# controller.net
KiCad netlist of a schematic drawn in EAGLE
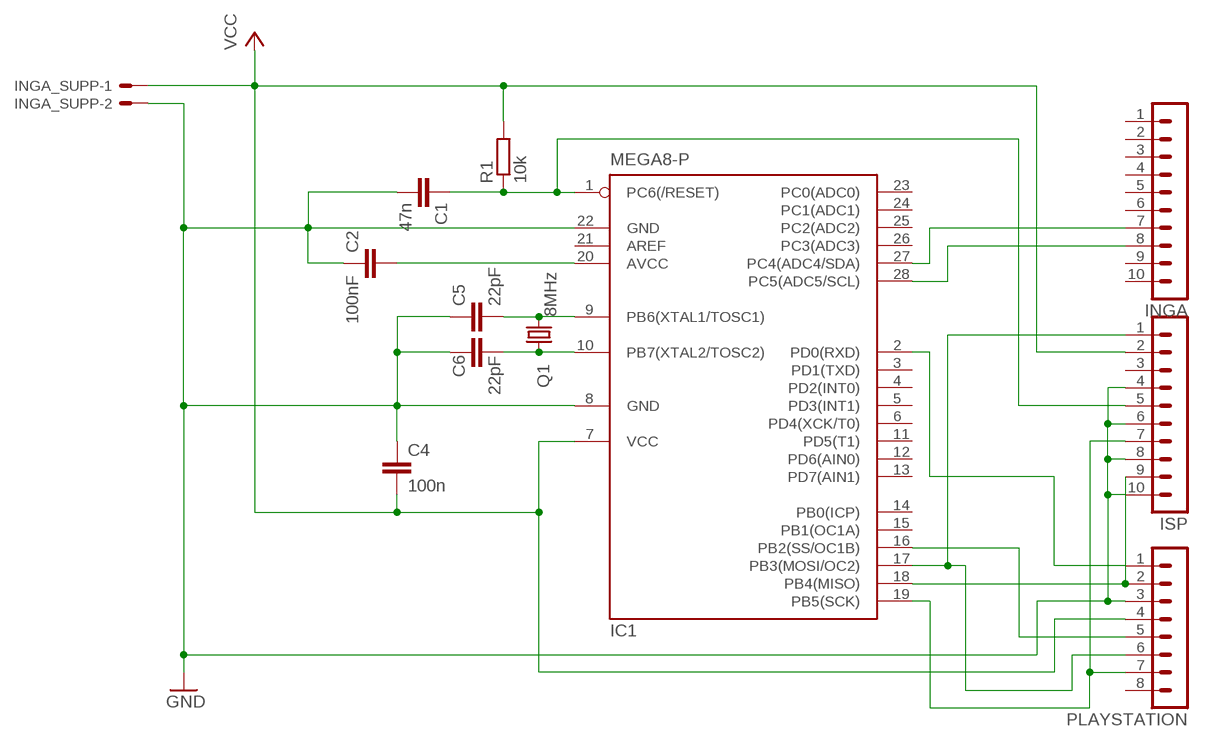
[diagram p0: schematic, sheet 1]

(export (version "E")
  (design (tool "Eeschema 10.0.6"))
  (components
    (comp (ref "C1")
      (value "47n")
      (footprint "eagle-import:C2.5-3")
      (libsource (lib "eagle-import") (part "C2,5-3"))
    )
    (comp (ref "C2")
      (value "100nF")
      (footprint "eagle-import:C2.5-3")
      (libsource (lib "eagle-import") (part "C2,5-3"))
    )
    (comp (ref "C4")
      (value "100n")
      (footprint "eagle-import:C2.5-3")
      (libsource (lib "eagle-import") (part "C2,5-3"))
    )
    (comp (ref "C5")
      (value "22pF")
      (footprint "eagle-import:C2.5-3")
      (libsource (lib "eagle-import") (part "C2,5-3"))
    )
    (comp (ref "C6")
      (value "22pF")
      (footprint "eagle-import:C2.5-3")
      (libsource (lib "eagle-import") (part "C2,5-3"))
    )
    (comp (ref "IC1")
      (value "MEGA8-P")
      (footprint "eagle-import:DIL28-3")
      (libsource (lib "eagle-import") (part "MEGA8-P"))
    )
    (comp (ref "INGA")
      (value "MA10-1")
      (footprint "eagle-import:MA10-1")
      (libsource (lib "eagle-import") (part "MA10-1"))
    )
    (comp (ref "INGA_SUPP")
      (value "22-23-2021")
      (footprint "eagle-import:22-23-2021")
      (fields (field (name "MF") "MOLEX"))
      (libsource (lib "eagle-import") (part "22-23-2021"))
    )
    (comp (ref "ISP")
      (value "MA10-1")
      (footprint "eagle-import:MA10-1")
      (libsource (lib "eagle-import") (part "MA10-1"))
    )
    (comp (ref "PLAYSTATION")
      (value "MA08-1")
      (footprint "eagle-import:MA08-1")
      (libsource (lib "eagle-import") (part "MA08-1"))
    )
    (comp (ref "Q1")
      (value "8MHz")
      (footprint "eagle-import:HC49U70")
      (libsource (lib "eagle-import") (part "CRYSTALHC49U70"))
    )
    (comp (ref "R1")
      (value "10k")
      (footprint "eagle-import:0207_10")
      (libsource (lib "eagle-import") (part "R-EU_0207/10"))
    )
  )
  (nets
    (net (code "1") (name "GND") (class "Default")
      (node (ref "C1") (pin "2") (pinfunction "2_2") (pintype "passive"))
      (node (ref "C2") (pin "1") (pinfunction "1_1") (pintype "passive"))
      (node (ref "C4") (pin "1") (pinfunction "1_1") (pintype "passive"))
      (node (ref "C5") (pin "1") (pinfunction "1_1") (pintype "passive"))
      (node (ref "C6") (pin "1") (pinfunction "1_1") (pintype "passive"))
      (node (ref "IC1") (pin "22") (pinfunction "GND_22") (pintype "power_in"))
      (node (ref "IC1") (pin "8") (pinfunction "GND_8") (pintype "power_in"))
      (node (ref "INGA_SUPP") (pin "2") (pinfunction "S_2") (pintype "passive"))
      (node (ref "ISP") (pin "10") (pinfunction "10_10") (pintype "passive"))
      (node (ref "ISP") (pin "4") (pinfunction "4_4") (pintype "passive"))
      (node (ref "ISP") (pin "6") (pinfunction "6_6") (pintype "passive"))
      (node (ref "ISP") (pin "8") (pinfunction "8_8") (pintype "passive"))
      (node (ref "PLAYSTATION") (pin "3") (pinfunction "3_3") (pintype "passive"))
    )
    (net (code "2") (name "Net-(IC1-AVCC)") (class "Default")
      (node (ref "C2") (pin "2") (pinfunction "2_2") (pintype "passive"))
      (node (ref "IC1") (pin "20") (pinfunction "AVCC_20") (pintype "power_in"))
    )
    (net (code "3") (name "Net-(IC1-PB2(SS{slash}OC1B))") (class "Default")
      (node (ref "IC1") (pin "16") (pinfunction "PB2(SS/OC1B)_16") (pintype "bidirectional"))
      (node (ref "PLAYSTATION") (pin "5") (pinfunction "5_5") (pintype "passive"))
    )
    (net (code "4") (name "Net-(IC1-PB3(MOSI{slash}OC2))") (class "Default")
      (node (ref "IC1") (pin "17") (pinfunction "PB3(MOSI/OC2)_17") (pintype "bidirectional"))
      (node (ref "ISP") (pin "1") (pinfunction "1_1") (pintype "passive"))
      (node (ref "PLAYSTATION") (pin "6") (pinfunction "6_6") (pintype "passive"))
    )
    (net (code "5") (name "Net-(IC1-PB4(MISO))") (class "Default")
      (node (ref "IC1") (pin "18") (pinfunction "PB4(MISO)_18") (pintype "bidirectional"))
      (node (ref "ISP") (pin "9") (pinfunction "9_9") (pintype "passive"))
      (node (ref "PLAYSTATION") (pin "2") (pinfunction "2_2") (pintype "passive"))
    )
    (net (code "6") (name "Net-(IC1-PB5(SCK))") (class "Default")
      (node (ref "IC1") (pin "19") (pinfunction "PB5(SCK)_19") (pintype "bidirectional"))
      (node (ref "ISP") (pin "7") (pinfunction "7_7") (pintype "passive"))
      (node (ref "PLAYSTATION") (pin "7") (pinfunction "7_7") (pintype "passive"))
    )
    (net (code "7") (name "Net-(IC1-PB6(XTAL1{slash}TOSC1))") (class "Default")
      (node (ref "C5") (pin "2") (pinfunction "2_2") (pintype "passive"))
      (node (ref "IC1") (pin "9") (pinfunction "PB6(XTAL1/TOSC1)_9") (pintype "bidirectional"))
      (node (ref "Q1") (pin "2") (pinfunction "2_2") (pintype "passive"))
    )
    (net (code "8") (name "Net-(IC1-PB7(XTAL2{slash}TOSC2))") (class "Default")
      (node (ref "C6") (pin "2") (pinfunction "2_2") (pintype "passive"))
      (node (ref "IC1") (pin "10") (pinfunction "PB7(XTAL2/TOSC2)_10") (pintype "bidirectional"))
      (node (ref "Q1") (pin "1") (pinfunction "1_1") (pintype "passive"))
    )
    (net (code "9") (name "Net-(IC1-PC4(ADC4{slash}SDA))") (class "Default")
      (node (ref "IC1") (pin "27") (pinfunction "PC4(ADC4/SDA)_27") (pintype "bidirectional"))
      (node (ref "INGA") (pin "7") (pinfunction "7_7") (pintype "passive"))
    )
    (net (code "10") (name "Net-(IC1-PC5(ADC5{slash}SCL))") (class "Default")
      (node (ref "IC1") (pin "28") (pinfunction "PC5(ADC5/SCL)_28") (pintype "bidirectional"))
      (node (ref "INGA") (pin "8") (pinfunction "8_8") (pintype "passive"))
    )
    (net (code "11") (name "Net-(IC1-PC6({slash}RESET))") (class "Default")
      (node (ref "C1") (pin "1") (pinfunction "1_1") (pintype "passive"))
      (node (ref "IC1") (pin "1") (pinfunction "PC6(/RESET)_1") (pintype "bidirectional"))
      (node (ref "ISP") (pin "5") (pinfunction "5_5") (pintype "passive"))
      (node (ref "R1") (pin "1") (pinfunction "1_1") (pintype "passive"))
    )
    (net (code "12") (name "Net-(IC1-PD0(RXD))") (class "Default")
      (node (ref "IC1") (pin "2") (pinfunction "PD0(RXD)_2") (pintype "bidirectional"))
      (node (ref "PLAYSTATION") (pin "1") (pinfunction "1_1") (pintype "passive"))
    )
    (net (code "13") (name "VCC") (class "Default")
      (node (ref "C4") (pin "2") (pinfunction "2_2") (pintype "passive"))
      (node (ref "IC1") (pin "7") (pinfunction "VCC_7") (pintype "power_in"))
      (node (ref "INGA_SUPP") (pin "1") (pinfunction "S_1") (pintype "passive"))
      (node (ref "ISP") (pin "2") (pinfunction "2_2") (pintype "passive"))
      (node (ref "PLAYSTATION") (pin "4") (pinfunction "4_4") (pintype "passive"))
      (node (ref "R1") (pin "2") (pinfunction "2_2") (pintype "passive"))
    )
    (net (code "14") (name "unconnected-(IC1-AREF-Pad21)") (class "Default")
      (node (ref "IC1") (pin "21") (pinfunction "AREF_21") (pintype "passive"))
    )
    (net (code "15") (name "unconnected-(IC1-PB0(ICP)-Pad14)") (class "Default")
      (node (ref "IC1") (pin "14") (pinfunction "PB0(ICP)_14") (pintype "bidirectional"))
    )
    (net (code "16") (name "unconnected-(IC1-PB1(OC1A)-Pad15)") (class "Default")
      (node (ref "IC1") (pin "15") (pinfunction "PB1(OC1A)_15") (pintype "bidirectional"))
    )
    (net (code "17") (name "unconnected-(IC1-PC0(ADC0)-Pad23)") (class "Default")
      (node (ref "IC1") (pin "23") (pinfunction "PC0(ADC0)_23") (pintype "bidirectional"))
    )
    (net (code "18") (name "unconnected-(IC1-PC1(ADC1)-Pad24)") (class "Default")
      (node (ref "IC1") (pin "24") (pinfunction "PC1(ADC1)_24") (pintype "bidirectional"))
    )
    (net (code "19") (name "unconnected-(IC1-PC2(ADC2)-Pad25)") (class "Default")
      (node (ref "IC1") (pin "25") (pinfunction "PC2(ADC2)_25") (pintype "bidirectional"))
    )
    (net (code "20") (name "unconnected-(IC1-PC3(ADC3)-Pad26)") (class "Default")
      (node (ref "IC1") (pin "26") (pinfunction "PC3(ADC3)_26") (pintype "bidirectional"))
    )
    (net (code "21") (name "unconnected-(IC1-PD1(TXD)-Pad3)") (class "Default")
      (node (ref "IC1") (pin "3") (pinfunction "PD1(TXD)_3") (pintype "bidirectional"))
    )
    (net (code "22") (name "unconnected-(IC1-PD2(INT0)-Pad4)") (class "Default")
      (node (ref "IC1") (pin "4") (pinfunction "PD2(INT0)_4") (pintype "bidirectional"))
    )
    (net (code "23") (name "unconnected-(IC1-PD3(INT1)-Pad5)") (class "Default")
      (node (ref "IC1") (pin "5") (pinfunction "PD3(INT1)_5") (pintype "bidirectional"))
    )
    (net (code "24") (name "unconnected-(IC1-PD4(XCK{slash}T0)-Pad6)") (class "Default")
      (node (ref "IC1") (pin "6") (pinfunction "PD4(XCK/T0)_6") (pintype "bidirectional"))
    )
    (net (code "25") (name "unconnected-(IC1-PD5(T1)-Pad11)") (class "Default")
      (node (ref "IC1") (pin "11") (pinfunction "PD5(T1)_11") (pintype "bidirectional"))
    )
    (net (code "26") (name "unconnected-(IC1-PD6(AIN0)-Pad12)") (class "Default")
      (node (ref "IC1") (pin "12") (pinfunction "PD6(AIN0)_12") (pintype "bidirectional"))
    )
    (net (code "27") (name "unconnected-(IC1-PD7(AIN1)-Pad13)") (class "Default")
      (node (ref "IC1") (pin "13") (pinfunction "PD7(AIN1)_13") (pintype "bidirectional"))
    )
    (net (code "28") (name "unconnected-(INGA-Pad1)") (class "Default")
      (node (ref "INGA") (pin "1") (pinfunction "1_1") (pintype "passive"))
    )
    (net (code "29") (name "unconnected-(INGA-Pad2)") (class "Default")
      (node (ref "INGA") (pin "2") (pinfunction "2_2") (pintype "passive"))
    )
    (net (code "30") (name "unconnected-(INGA-Pad3)") (class "Default")
      (node (ref "INGA") (pin "3") (pinfunction "3_3") (pintype "passive"))
    )
    (net (code "31") (name "unconnected-(INGA-Pad4)") (class "Default")
      (node (ref "INGA") (pin "4") (pinfunction "4_4") (pintype "passive"))
    )
    (net (code "32") (name "unconnected-(INGA-Pad5)") (class "Default")
      (node (ref "INGA") (pin "5") (pinfunction "5_5") (pintype "passive"))
    )
    (net (code "33") (name "unconnected-(INGA-Pad6)") (class "Default")
      (node (ref "INGA") (pin "6") (pinfunction "6_6") (pintype "passive"))
    )
    (net (code "34") (name "unconnected-(INGA-Pad9)") (class "Default")
      (node (ref "INGA") (pin "9") (pinfunction "9_9") (pintype "passive"))
    )
    (net (code "35") (name "unconnected-(INGA-Pad10)") (class "Default")
      (node (ref "INGA") (pin "10") (pinfunction "10_10") (pintype "passive"))
    )
    (net (code "36") (name "unconnected-(ISP-Pad3)") (class "Default")
      (node (ref "ISP") (pin "3") (pinfunction "3_3") (pintype "passive"))
    )
    (net (code "37") (name "unconnected-(PLAYSTATION-Pad8)") (class "Default")
      (node (ref "PLAYSTATION") (pin "8") (pinfunction "8_8") (pintype "passive"))
    )
  )
)
